# PERIPHERAL.net
KiCad netlist of a schematic drawn in Altium Designer
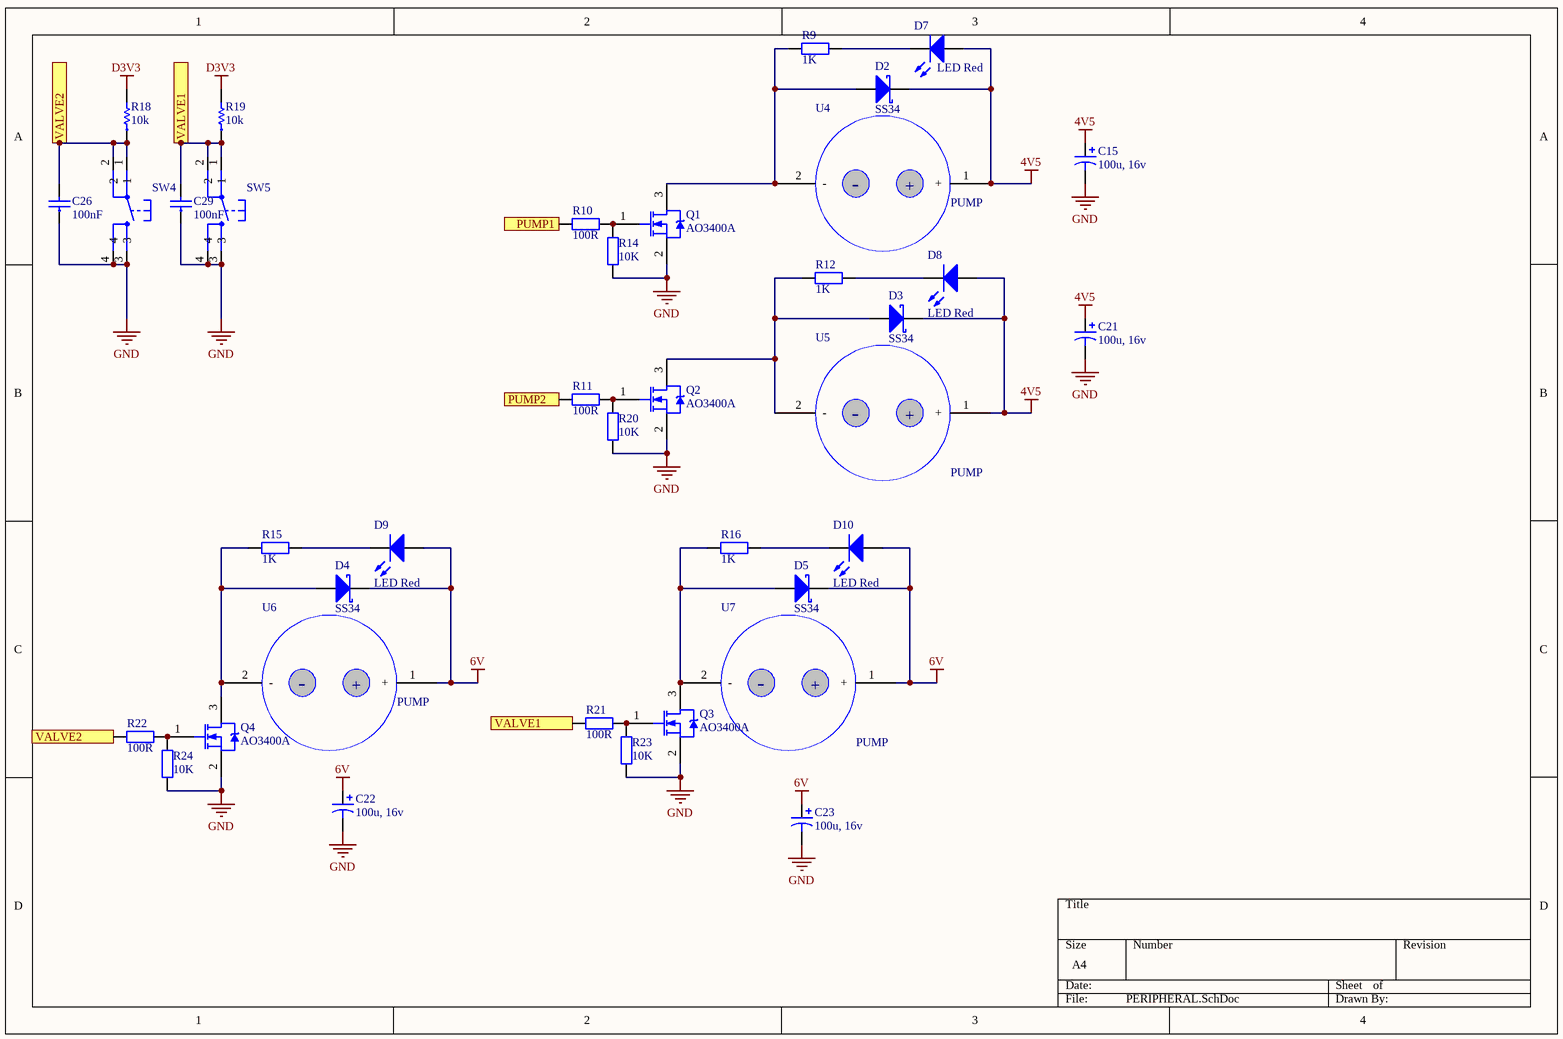
[diagram p0: PERIPHERAL.SchDoc]

(export (version "E")
  (design (tool "Eeschema 10.0.6"))
  (components
    (comp (ref "C15")
      (value "100u, 16v")
      (footprint "CAPACITOR SIZE_D(D6.6)")
      (description "CAP ALUM 100UF 20% 16V SMD")
      (libsource (lib "capacitor") (part "UWT1C101MCL1GB"))
    )
    (comp (ref "C21")
      (value "100u, 16v")
      (footprint "CAPACITOR SIZE_D(D6.6)")
      (description "CAP ALUM 100UF 20% 16V SMD")
      (libsource (lib "capacitor") (part "UWT1C101MCL1GB"))
    )
    (comp (ref "C22")
      (value "100u, 16v")
      (footprint "CAPACITOR SIZE_D(D6.6)")
      (description "CAP ALUM 100UF 20% 16V SMD")
      (libsource (lib "capacitor") (part "UWT1C101MCL1GB"))
    )
    (comp (ref "C23")
      (value "100u, 16v")
      (footprint "CAPACITOR SIZE_D(D6.6)")
      (description "CAP ALUM 100UF 20% 16V SMD")
      (libsource (lib "capacitor") (part "UWT1C101MCL1GB"))
    )
    (comp (ref "C26")
      (value "100nF")
      (footprint "C0603")
      (description "CAP CER 100nF 10% 50V X7R 0603 SMD")
      (libsource (lib "2502-GMQLITE-MAIN") (part "CAPCER0001 100nF 10% 50V X7R 0603 SMD"))
    )
    (comp (ref "C29")
      (value "100nF")
      (footprint "C0603")
      (description "CAP CER 100nF 10% 50V X7R 0603 SMD")
      (libsource (lib "2502-GMQLITE-MAIN") (part "CAPCER0001 100nF 10% 50V X7R 0603 SMD"))
    )
    (comp (ref "D2")
      (value "SS34")
      (footprint "DO-214AC")
      (description "Schottky Diode 40V 3A SMA")
      (libsource (lib "diode") (part "SS34"))
    )
    (comp (ref "D3")
      (value "SS34")
      (footprint "DO-214AC")
      (description "Schottky Diode 40V 3A SMA")
      (libsource (lib "diode") (part "SS34"))
    )
    (comp (ref "D4")
      (value "SS34")
      (footprint "DO-214AC")
      (description "Schottky Diode 40V 3A SMA")
      (libsource (lib "diode") (part "SS34"))
    )
    (comp (ref "D5")
      (value "SS34")
      (footprint "DO-214AC")
      (description "Schottky Diode 40V 3A SMA")
      (libsource (lib "diode") (part "SS34"))
    )
    (comp (ref "D7")
      (value "LED Red")
      (footprint "LED0603-R")
      (description "Lite-On LED Red 0603")
      (libsource (lib "diode") (part "LTST-C190KRKT"))
    )
    (comp (ref "D8")
      (value "LED Red")
      (footprint "LED0603-R")
      (description "Lite-On LED Red 0603")
      (libsource (lib "diode") (part "LTST-C190KRKT"))
    )
    (comp (ref "D9")
      (value "LED Red")
      (footprint "LED0603-R")
      (description "Lite-On LED Red 0603")
      (libsource (lib "diode") (part "LTST-C190KRKT"))
    )
    (comp (ref "D10")
      (value "LED Red")
      (footprint "LED0603-R")
      (description "Lite-On LED Red 0603")
      (libsource (lib "diode") (part "LTST-C190KRKT"))
    )
    (comp (ref "Q1")
      (value "AO3400A")
      (footprint "SOT-23")
      (description "MOSFET N-CH 25V 5.8A SOT23")
      (libsource (lib "fet") (part "IRFML8244TRPBF"))
    )
    (comp (ref "Q2")
      (value "AO3400A")
      (footprint "SOT-23")
      (description "MOSFET N-CH 25V 5.8A SOT23")
      (libsource (lib "fet") (part "IRFML8244TRPBF"))
    )
    (comp (ref "Q3")
      (value "AO3400A")
      (footprint "SOT-23")
      (description "MOSFET N-CH 25V 5.8A SOT23")
      (libsource (lib "fet") (part "IRFML8244TRPBF"))
    )
    (comp (ref "Q4")
      (value "AO3400A")
      (footprint "SOT-23")
      (description "MOSFET N-CH 25V 5.8A SOT23")
      (libsource (lib "fet") (part "IRFML8244TRPBF"))
    )
    (comp (ref "R9")
      (value "1K")
      (footprint "R0603")
      (description "Yageo RES 1K 5% 1/10W 0603")
      (fields (field (name "Comment") "RES 1K 5% 1/10W 0603"))
      (libsource (lib "resistor") (part "RC0603JR-071KL"))
    )
    (comp (ref "R10")
      (value "100R")
      (footprint "R0603")
      (description "Yageo RES 100R 5% 1/10W 0603")
      (fields (field (name "Comment") "RES 100R 5% 1/10W 0603"))
      (libsource (lib "resistor") (part "RC0603JR-07100RL"))
    )
    (comp (ref "R11")
      (value "100R")
      (footprint "R0603")
      (description "Yageo RES 100R 5% 1/10W 0603")
      (fields (field (name "Comment") "RES 100R 5% 1/10W 0603"))
      (libsource (lib "resistor") (part "RC0603JR-07100RL"))
    )
    (comp (ref "R12")
      (value "1K")
      (footprint "R0603")
      (description "Yageo RES 1K 5% 1/10W 0603")
      (fields (field (name "Comment") "RES 1K 5% 1/10W 0603"))
      (libsource (lib "resistor") (part "RC0603JR-071KL"))
    )
    (comp (ref "R14")
      (value "10K")
      (footprint "R0603")
      (description "Yageo RES 10K 5% 1/10W 0603")
      (fields (field (name "Comment") "RES 10K 5% 1/10W 0603"))
      (libsource (lib "resistor") (part "RC0603JR-0710KL"))
    )
    (comp (ref "R15")
      (value "1K")
      (footprint "R0603")
      (description "Yageo RES 1K 5% 1/10W 0603")
      (fields (field (name "Comment") "RES 1K 5% 1/10W 0603"))
      (libsource (lib "resistor") (part "RC0603JR-071KL"))
    )
    (comp (ref "R16")
      (value "1K")
      (footprint "R0603")
      (description "Yageo RES 1K 5% 1/10W 0603")
      (fields (field (name "Comment") "RES 1K 5% 1/10W 0603"))
      (libsource (lib "resistor") (part "RC0603JR-071KL"))
    )
    (comp (ref "R18")
      (value "10k")
      (footprint "R0603")
      (description "RES CHP 8K4 1% 1/10W 0603 SMD")
      (libsource (lib "2502-GMQLITE-MAIN") (part "RESCHP0428 8K4 1% 0603 SMD"))
    )
    (comp (ref "R19")
      (value "10k")
      (footprint "R0603")
      (description "RES CHP 8K4 1% 1/10W 0603 SMD")
      (libsource (lib "2502-GMQLITE-MAIN") (part "RESCHP0428 8K4 1% 0603 SMD"))
    )
    (comp (ref "R20")
      (value "10K")
      (footprint "R0603")
      (description "Yageo RES 10K 5% 1/10W 0603")
      (fields (field (name "Comment") "RES 10K 5% 1/10W 0603"))
      (libsource (lib "resistor") (part "RC0603JR-0710KL"))
    )
    (comp (ref "R21")
      (value "100R")
      (footprint "R0603")
      (description "Yageo RES 100R 5% 1/10W 0603")
      (fields (field (name "Comment") "RES 100R 5% 1/10W 0603"))
      (libsource (lib "resistor") (part "RC0603JR-07100RL"))
    )
    (comp (ref "R22")
      (value "100R")
      (footprint "R0603")
      (description "Yageo RES 100R 5% 1/10W 0603")
      (fields (field (name "Comment") "RES 100R 5% 1/10W 0603"))
      (libsource (lib "resistor") (part "RC0603JR-07100RL"))
    )
    (comp (ref "R23")
      (value "10K")
      (footprint "R0603")
      (description "Yageo RES 10K 5% 1/10W 0603")
      (fields (field (name "Comment") "RES 10K 5% 1/10W 0603"))
      (libsource (lib "resistor") (part "RC0603JR-0710KL"))
    )
    (comp (ref "R24")
      (value "10K")
      (footprint "R0603")
      (description "Yageo RES 10K 5% 1/10W 0603")
      (fields (field (name "Comment") "RES 10K 5% 1/10W 0603"))
      (libsource (lib "resistor") (part "RC0603JR-0710KL"))
    )
    (comp (ref "SW4")
      (value "SW2")
      (footprint "SWITCH")
      (description "Switch button 4 pin")
      (libsource (lib "Stm32_Flyback_Driver_250814_1") (part "SW2"))
    )
    (comp (ref "SW5")
      (value "SW2")
      (footprint "SWITCH")
      (description "Switch button 4 pin")
      (libsource (lib "Stm32_Flyback_Driver_250814_1") (part "SW2"))
    )
    (comp (ref "U4")
      (value "PUMP")
      (footprint "Pump")
      (description "Connector Header 2 Position 6.35mm Solder Straight Thru-Hole 2 Terminal 1 Port MLX-Series")
      (fields (field (name "MANUFACTURER") "Molex") (field (name "MANUFACTURER PART NUMBER") "10-84-4022"))
      (libsource (lib "LIB_PRESSURE") (part "A5F083"))
    )
    (comp (ref "U5")
      (value "PUMP")
      (footprint "Pump")
      (description "Connector Header 2 Position 6.35mm Solder Straight Thru-Hole 2 Terminal 1 Port MLX-Series")
      (fields (field (name "MANUFACTURER") "Molex") (field (name "MANUFACTURER PART NUMBER") "10-84-4022"))
      (libsource (lib "LIB_PRESSURE") (part "A5F083"))
    )
    (comp (ref "U6")
      (value "PUMP")
      (footprint "VALVE")
      (description "Connector Header 2 Position 6.35mm Solder Straight Thru-Hole 2 Terminal 1 Port MLX-Series")
      (fields (field (name "MANUFACTURER") "Molex") (field (name "MANUFACTURER PART NUMBER") "10-84-4022"))
      (libsource (lib "LIB_PRESSURE") (part "A5F083"))
    )
    (comp (ref "U7")
      (value "PUMP")
      (footprint "VALVE")
      (description "Connector Header 2 Position 6.35mm Solder Straight Thru-Hole 2 Terminal 1 Port MLX-Series")
      (fields (field (name "MANUFACTURER") "Molex") (field (name "MANUFACTURER PART NUMBER") "10-84-4022"))
      (libsource (lib "LIB_PRESSURE") (part "A5F083"))
    )
  )
  (nets
    (net (code "1") (name "/PUMP1") (class "Default")
      (node (ref "R10") (pin "1") (pinfunction "1_1") (pintype "passive"))
    )
    (net (code "2") (name "/PUMP2") (class "Default")
      (node (ref "R11") (pin "1") (pinfunction "1_1") (pintype "passive"))
    )
    (net (code "3") (name "/VALVE1") (class "Default")
      (node (ref "C29") (pin "2") (pinfunction "2_2") (pintype "passive"))
      (node (ref "R19") (pin "1") (pinfunction "1_1") (pintype "passive"))
      (node (ref "R21") (pin "1") (pinfunction "1_1") (pintype "passive"))
      (node (ref "SW5") (pin "1") (pinfunction "1_1") (pintype "passive"))
      (node (ref "SW5") (pin "2") (pinfunction "2_2") (pintype "passive"))
    )
    (net (code "4") (name "/VALVE2") (class "Default")
      (node (ref "C26") (pin "2") (pinfunction "2_2") (pintype "passive"))
      (node (ref "R18") (pin "1") (pinfunction "1_1") (pintype "passive"))
      (node (ref "R22") (pin "1") (pinfunction "1_1") (pintype "passive"))
      (node (ref "SW4") (pin "1") (pinfunction "1_1") (pintype "passive"))
      (node (ref "SW4") (pin "2") (pinfunction "2_2") (pintype "passive"))
    )
    (net (code "5") (name "4V5") (class "Default")
      (node (ref "C15") (pin "1") (pinfunction "1_1") (pintype "passive"))
      (node (ref "C21") (pin "1") (pinfunction "1_1") (pintype "passive"))
      (node (ref "D2") (pin "2") (pinfunction "K_2") (pintype "passive"))
      (node (ref "D3") (pin "2") (pinfunction "K_2") (pintype "passive"))
      (node (ref "D7") (pin "1") (pinfunction "A_1") (pintype "passive"))
      (node (ref "D8") (pin "1") (pinfunction "A_1") (pintype "passive"))
      (node (ref "U4") (pin "1") (pinfunction "+_1") (pintype "passive"))
      (node (ref "U5") (pin "1") (pinfunction "+_1") (pintype "passive"))
    )
    (net (code "6") (name "6V") (class "Default")
      (node (ref "C22") (pin "1") (pinfunction "1_1") (pintype "passive"))
      (node (ref "C23") (pin "1") (pinfunction "1_1") (pintype "passive"))
      (node (ref "D10") (pin "1") (pinfunction "A_1") (pintype "passive"))
      (node (ref "D4") (pin "2") (pinfunction "K_2") (pintype "passive"))
      (node (ref "D5") (pin "2") (pinfunction "K_2") (pintype "passive"))
      (node (ref "D9") (pin "1") (pinfunction "A_1") (pintype "passive"))
      (node (ref "U6") (pin "1") (pinfunction "+_1") (pintype "passive"))
      (node (ref "U7") (pin "1") (pinfunction "+_1") (pintype "passive"))
    )
    (net (code "7") (name "D3V3") (class "Default")
      (node (ref "R18") (pin "2") (pinfunction "2_2") (pintype "passive"))
      (node (ref "R19") (pin "2") (pinfunction "2_2") (pintype "passive"))
    )
    (net (code "8") (name "GND") (class "Default")
      (node (ref "C15") (pin "2") (pinfunction "2_2") (pintype "passive"))
      (node (ref "C21") (pin "2") (pinfunction "2_2") (pintype "passive"))
      (node (ref "C22") (pin "2") (pinfunction "2_2") (pintype "passive"))
      (node (ref "C23") (pin "2") (pinfunction "2_2") (pintype "passive"))
      (node (ref "C26") (pin "1") (pinfunction "1_1") (pintype "passive"))
      (node (ref "C29") (pin "1") (pinfunction "1_1") (pintype "passive"))
      (node (ref "Q1") (pin "2") (pinfunction "S_2") (pintype "passive"))
      (node (ref "Q2") (pin "2") (pinfunction "S_2") (pintype "passive"))
      (node (ref "Q3") (pin "2") (pinfunction "S_2") (pintype "passive"))
      (node (ref "Q4") (pin "2") (pinfunction "S_2") (pintype "passive"))
      (node (ref "R14") (pin "1") (pinfunction "1_1") (pintype "passive"))
      (node (ref "R20") (pin "1") (pinfunction "1_1") (pintype "passive"))
      (node (ref "R23") (pin "1") (pinfunction "1_1") (pintype "passive"))
      (node (ref "R24") (pin "1") (pinfunction "1_1") (pintype "passive"))
      (node (ref "SW4") (pin "3") (pinfunction "3_3") (pintype "passive"))
      (node (ref "SW4") (pin "4") (pinfunction "4_4") (pintype "passive"))
      (node (ref "SW5") (pin "3") (pinfunction "3_3") (pintype "passive"))
      (node (ref "SW5") (pin "4") (pinfunction "4_4") (pintype "passive"))
    )
    (net (code "9") (name "Net-(D2-A)") (class "Default")
      (node (ref "D2") (pin "1") (pinfunction "A_1") (pintype "passive"))
      (node (ref "Q1") (pin "3") (pinfunction "D_3") (pintype "passive"))
      (node (ref "R9") (pin "1") (pinfunction "1_1") (pintype "passive"))
      (node (ref "U4") (pin "2") (pinfunction "-_2") (pintype "passive"))
    )
    (net (code "10") (name "Net-(D3-A)") (class "Default")
      (node (ref "D3") (pin "1") (pinfunction "A_1") (pintype "passive"))
      (node (ref "Q2") (pin "3") (pinfunction "D_3") (pintype "passive"))
      (node (ref "R12") (pin "1") (pinfunction "1_1") (pintype "passive"))
      (node (ref "U5") (pin "2") (pinfunction "-_2") (pintype "passive"))
    )
    (net (code "11") (name "Net-(D4-A)") (class "Default")
      (node (ref "D4") (pin "1") (pinfunction "A_1") (pintype "passive"))
      (node (ref "Q4") (pin "3") (pinfunction "D_3") (pintype "passive"))
      (node (ref "R15") (pin "1") (pinfunction "1_1") (pintype "passive"))
      (node (ref "U6") (pin "2") (pinfunction "-_2") (pintype "passive"))
    )
    (net (code "12") (name "Net-(D5-A)") (class "Default")
      (node (ref "D5") (pin "1") (pinfunction "A_1") (pintype "passive"))
      (node (ref "Q3") (pin "3") (pinfunction "D_3") (pintype "passive"))
      (node (ref "R16") (pin "1") (pinfunction "1_1") (pintype "passive"))
      (node (ref "U7") (pin "2") (pinfunction "-_2") (pintype "passive"))
    )
    (net (code "13") (name "Net-(D7-K)") (class "Default")
      (node (ref "D7") (pin "2") (pinfunction "K_2") (pintype "passive"))
      (node (ref "R9") (pin "2") (pinfunction "2_2") (pintype "passive"))
    )
    (net (code "14") (name "Net-(D8-K)") (class "Default")
      (node (ref "D8") (pin "2") (pinfunction "K_2") (pintype "passive"))
      (node (ref "R12") (pin "2") (pinfunction "2_2") (pintype "passive"))
    )
    (net (code "15") (name "Net-(D9-K)") (class "Default")
      (node (ref "D9") (pin "2") (pinfunction "K_2") (pintype "passive"))
      (node (ref "R15") (pin "2") (pinfunction "2_2") (pintype "passive"))
    )
    (net (code "16") (name "Net-(D10-K)") (class "Default")
      (node (ref "D10") (pin "2") (pinfunction "K_2") (pintype "passive"))
      (node (ref "R16") (pin "2") (pinfunction "2_2") (pintype "passive"))
    )
    (net (code "17") (name "Net-(Q1-G)") (class "Default")
      (node (ref "Q1") (pin "1") (pinfunction "G_1") (pintype "passive"))
      (node (ref "R10") (pin "2") (pinfunction "2_2") (pintype "passive"))
      (node (ref "R14") (pin "2") (pinfunction "2_2") (pintype "passive"))
    )
    (net (code "18") (name "Net-(Q2-G)") (class "Default")
      (node (ref "Q2") (pin "1") (pinfunction "G_1") (pintype "passive"))
      (node (ref "R11") (pin "2") (pinfunction "2_2") (pintype "passive"))
      (node (ref "R20") (pin "2") (pinfunction "2_2") (pintype "passive"))
    )
    (net (code "19") (name "Net-(Q3-G)") (class "Default")
      (node (ref "Q3") (pin "1") (pinfunction "G_1") (pintype "passive"))
      (node (ref "R21") (pin "2") (pinfunction "2_2") (pintype "passive"))
      (node (ref "R23") (pin "2") (pinfunction "2_2") (pintype "passive"))
    )
    (net (code "20") (name "Net-(Q4-G)") (class "Default")
      (node (ref "Q4") (pin "1") (pinfunction "G_1") (pintype "passive"))
      (node (ref "R22") (pin "2") (pinfunction "2_2") (pintype "passive"))
      (node (ref "R24") (pin "2") (pinfunction "2_2") (pintype "passive"))
    )
  )
)
